# Top.net
KiCad netlist of a schematic drawn in Altium Designer
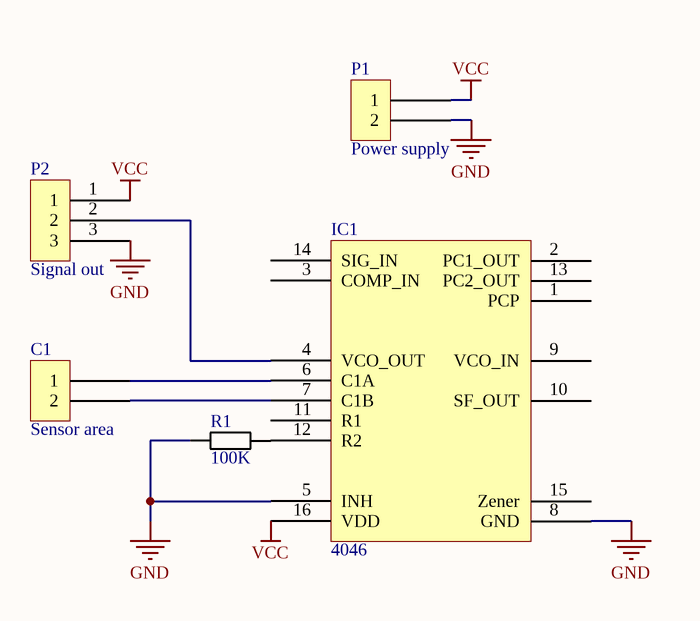
[diagram p0: Top.SchDoc]

(export (version "E")
  (design (tool "Eeschema 10.0.6"))
  (components
    (comp (ref "C1")
      (value "Sensor area")
      (footprint "Header 2x1 long")
      (libsource (lib "Headers") (part "Header 2x1"))
    )
    (comp (ref "IC1")
      (value "4046")
      (footprint "DIP-16")
      (description "PLL / VCO")
      (libsource (lib "ICs") (part "4046"))
    )
    (comp (ref "P1")
      (value "Power supply")
      (footprint "Header 2x1 long")
      (libsource (lib "Headers") (part "Header 2x1"))
    )
    (comp (ref "P2")
      (value "Signal out")
      (footprint "Header 3x1 long")
      (description "2.54mm")
      (libsource (lib "Headers") (part "Header 1x3"))
    )
    (comp (ref "R1")
      (value "100K")
      (footprint "R 0805 / 2012")
      (libsource (lib "Standard") (part "Resistor"))
    )
  )
  (nets
    (net (code "1") (name "GND") (class "Default")
      (node (ref "IC1") (pin "5") (pinfunction "INH_5") (pintype "passive"))
      (node (ref "IC1") (pin "8") (pinfunction "GND_8") (pintype "passive"))
      (node (ref "P1") (pin "2") (pinfunction "2_2") (pintype "passive"))
      (node (ref "P2") (pin "3") (pinfunction "3_3") (pintype "passive"))
      (node (ref "R1") (pin "2") (pinfunction "2_2") (pintype "passive"))
    )
    (net (code "2") (name "Net-(IC1-C1A)") (class "Default")
      (node (ref "C1") (pin "1") (pinfunction "1_1") (pintype "passive"))
      (node (ref "IC1") (pin "6") (pinfunction "C1A_6") (pintype "passive"))
    )
    (net (code "3") (name "Net-(IC1-C1B)") (class "Default")
      (node (ref "C1") (pin "2") (pinfunction "2_2") (pintype "passive"))
      (node (ref "IC1") (pin "7") (pinfunction "C1B_7") (pintype "passive"))
    )
    (net (code "4") (name "Net-(IC1-R2)") (class "Default")
      (node (ref "IC1") (pin "12") (pinfunction "R2_12") (pintype "passive"))
      (node (ref "R1") (pin "1") (pinfunction "1_1") (pintype "passive"))
    )
    (net (code "5") (name "Net-(IC1-VCO_OUT)") (class "Default")
      (node (ref "IC1") (pin "4") (pinfunction "VCO_OUT_4") (pintype "passive"))
      (node (ref "P2") (pin "2") (pinfunction "2_2") (pintype "passive"))
    )
    (net (code "6") (name "VCC") (class "Default")
      (node (ref "IC1") (pin "16") (pinfunction "VDD_16") (pintype "passive"))
      (node (ref "P1") (pin "1") (pinfunction "1_1") (pintype "passive"))
      (node (ref "P2") (pin "1") (pinfunction "1_1") (pintype "passive"))
    )
    (net (code "7") (name "unconnected-(IC1-COMP_IN-Pad3)") (class "Default")
      (node (ref "IC1") (pin "3") (pinfunction "COMP_IN_3") (pintype "passive"))
    )
    (net (code "8") (name "unconnected-(IC1-PC1_OUT-Pad2)") (class "Default")
      (node (ref "IC1") (pin "2") (pinfunction "PC1_OUT_2") (pintype "passive"))
    )
    (net (code "9") (name "unconnected-(IC1-PC2_OUT-Pad13)") (class "Default")
      (node (ref "IC1") (pin "13") (pinfunction "PC2_OUT_13") (pintype "passive"))
    )
    (net (code "10") (name "unconnected-(IC1-PCP-Pad1)") (class "Default")
      (node (ref "IC1") (pin "1") (pinfunction "PCP_1") (pintype "passive"))
    )
    (net (code "11") (name "unconnected-(IC1-R1-Pad11)") (class "Default")
      (node (ref "IC1") (pin "11") (pinfunction "R1_11") (pintype "passive"))
    )
    (net (code "12") (name "unconnected-(IC1-SF_OUT-Pad10)") (class "Default")
      (node (ref "IC1") (pin "10") (pinfunction "SF_OUT_10") (pintype "passive"))
    )
    (net (code "13") (name "unconnected-(IC1-SIG_IN-Pad14)") (class "Default")
      (node (ref "IC1") (pin "14") (pinfunction "SIG_IN_14") (pintype "passive"))
    )
    (net (code "14") (name "unconnected-(IC1-VCO_IN-Pad9)") (class "Default")
      (node (ref "IC1") (pin "9") (pinfunction "VCO_IN_9") (pintype "passive"))
    )
    (net (code "15") (name "unconnected-(IC1-Zener-Pad15)") (class "Default")
      (node (ref "IC1") (pin "15") (pinfunction "Zener_15") (pintype "passive"))
    )
  )
)
